# Component_Part1.net
KiCad netlist of a schematic drawn in Altium Designer
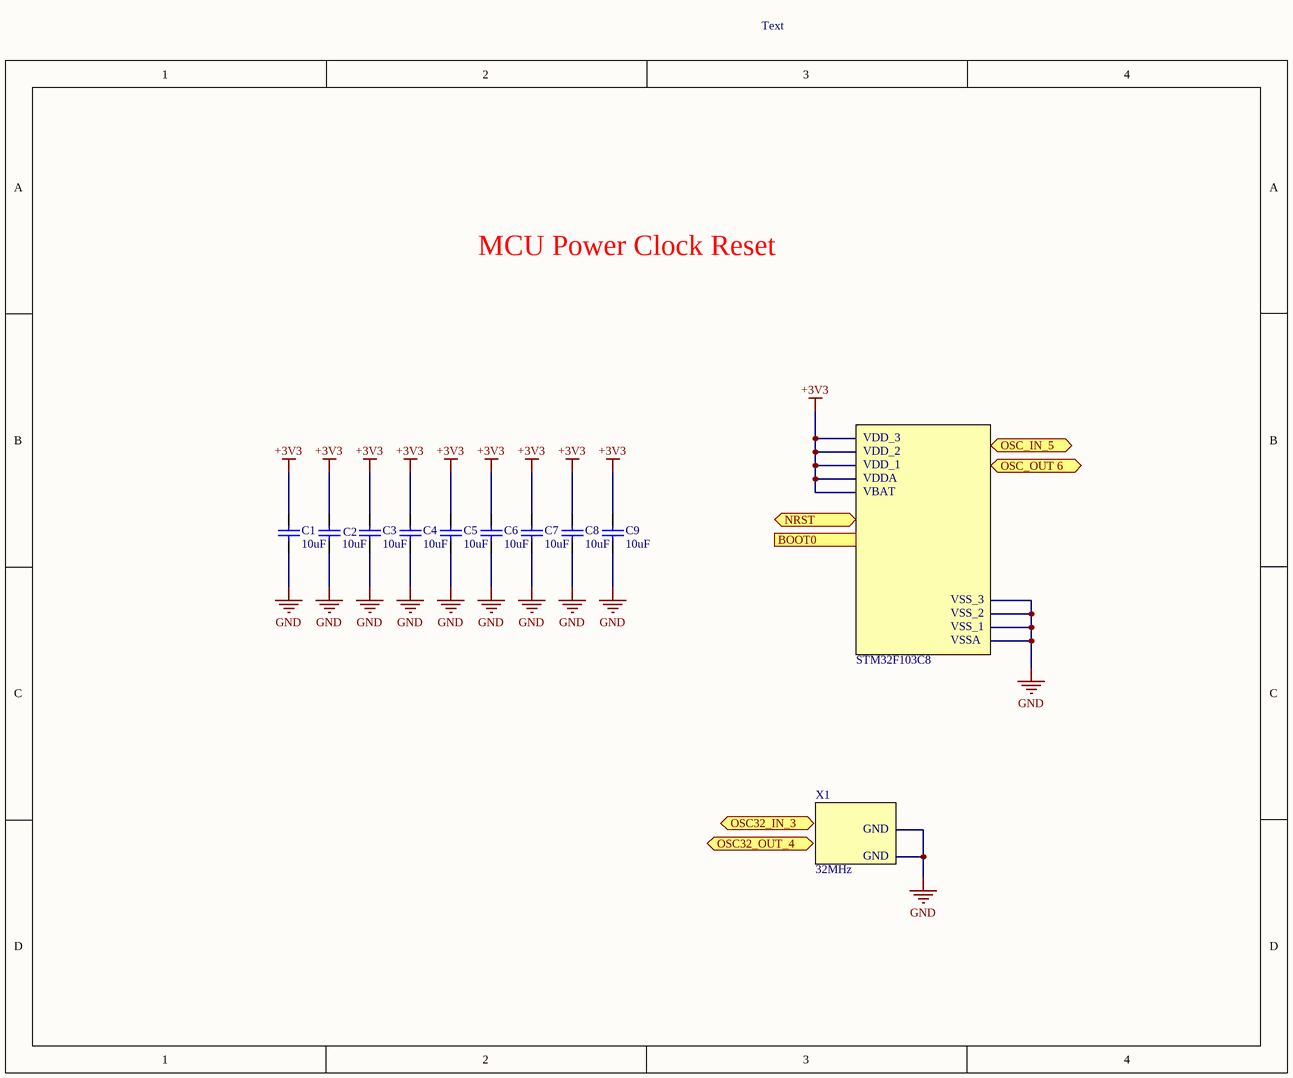
[diagram p0: Component_Part1.SchDoc]

(export (version "E")
  (design (tool "Eeschema 10.0.6"))
  (components
    (comp (ref "C1")
      (value "10uF")
      (description "Capacitor")
      (libsource (lib "Simulation Generic Components") (part "Capacitor"))
    )
    (comp (ref "C2")
      (value "10uF")
      (description "Capacitor")
      (libsource (lib "Simulation Generic Components") (part "Capacitor"))
    )
    (comp (ref "C3")
      (value "10uF")
      (description "Capacitor")
      (libsource (lib "Simulation Generic Components") (part "Capacitor"))
    )
    (comp (ref "C4")
      (value "10uF")
      (description "Capacitor")
      (libsource (lib "Simulation Generic Components") (part "Capacitor"))
    )
    (comp (ref "C5")
      (value "10uF")
      (description "Capacitor")
      (libsource (lib "Simulation Generic Components") (part "Capacitor"))
    )
    (comp (ref "C6")
      (value "10uF")
      (description "Capacitor")
      (libsource (lib "Simulation Generic Components") (part "Capacitor"))
    )
    (comp (ref "C7")
      (value "10uF")
      (description "Capacitor")
      (libsource (lib "Simulation Generic Components") (part "Capacitor"))
    )
    (comp (ref "C8")
      (value "10uF")
      (description "Capacitor")
      (libsource (lib "Simulation Generic Components") (part "Capacitor"))
    )
    (comp (ref "C9")
      (value "10uF")
      (description "Capacitor")
      (libsource (lib "Simulation Generic Components") (part "Capacitor"))
    )
  )
  (nets
    (net (code "1") (name "+3V3") (class "Default")
      (node (ref "C1") (pin "1") (pinfunction "1_1") (pintype "passive"))
      (node (ref "C2") (pin "1") (pinfunction "1_1") (pintype "passive"))
      (node (ref "C3") (pin "1") (pinfunction "1_1") (pintype "passive"))
      (node (ref "C4") (pin "1") (pinfunction "1_1") (pintype "passive"))
      (node (ref "C5") (pin "1") (pinfunction "1_1") (pintype "passive"))
      (node (ref "C6") (pin "1") (pinfunction "1_1") (pintype "passive"))
      (node (ref "C7") (pin "1") (pinfunction "1_1") (pintype "passive"))
      (node (ref "C8") (pin "1") (pinfunction "1_1") (pintype "passive"))
      (node (ref "C9") (pin "1") (pinfunction "1_1") (pintype "passive"))
    )
    (net (code "8") (name "GND") (class "Default")
      (node (ref "C1") (pin "2") (pinfunction "2_2") (pintype "passive"))
      (node (ref "C2") (pin "2") (pinfunction "2_2") (pintype "passive"))
      (node (ref "C3") (pin "2") (pinfunction "2_2") (pintype "passive"))
      (node (ref "C4") (pin "2") (pinfunction "2_2") (pintype "passive"))
      (node (ref "C5") (pin "2") (pinfunction "2_2") (pintype "passive"))
      (node (ref "C6") (pin "2") (pinfunction "2_2") (pintype "passive"))
      (node (ref "C7") (pin "2") (pinfunction "2_2") (pintype "passive"))
      (node (ref "C8") (pin "2") (pinfunction "2_2") (pintype "passive"))
      (node (ref "C9") (pin "2") (pinfunction "2_2") (pintype "passive"))
    )
  )
)
